# Board_no_0R.net
KiCad netlist of a schematic drawn in EAGLE
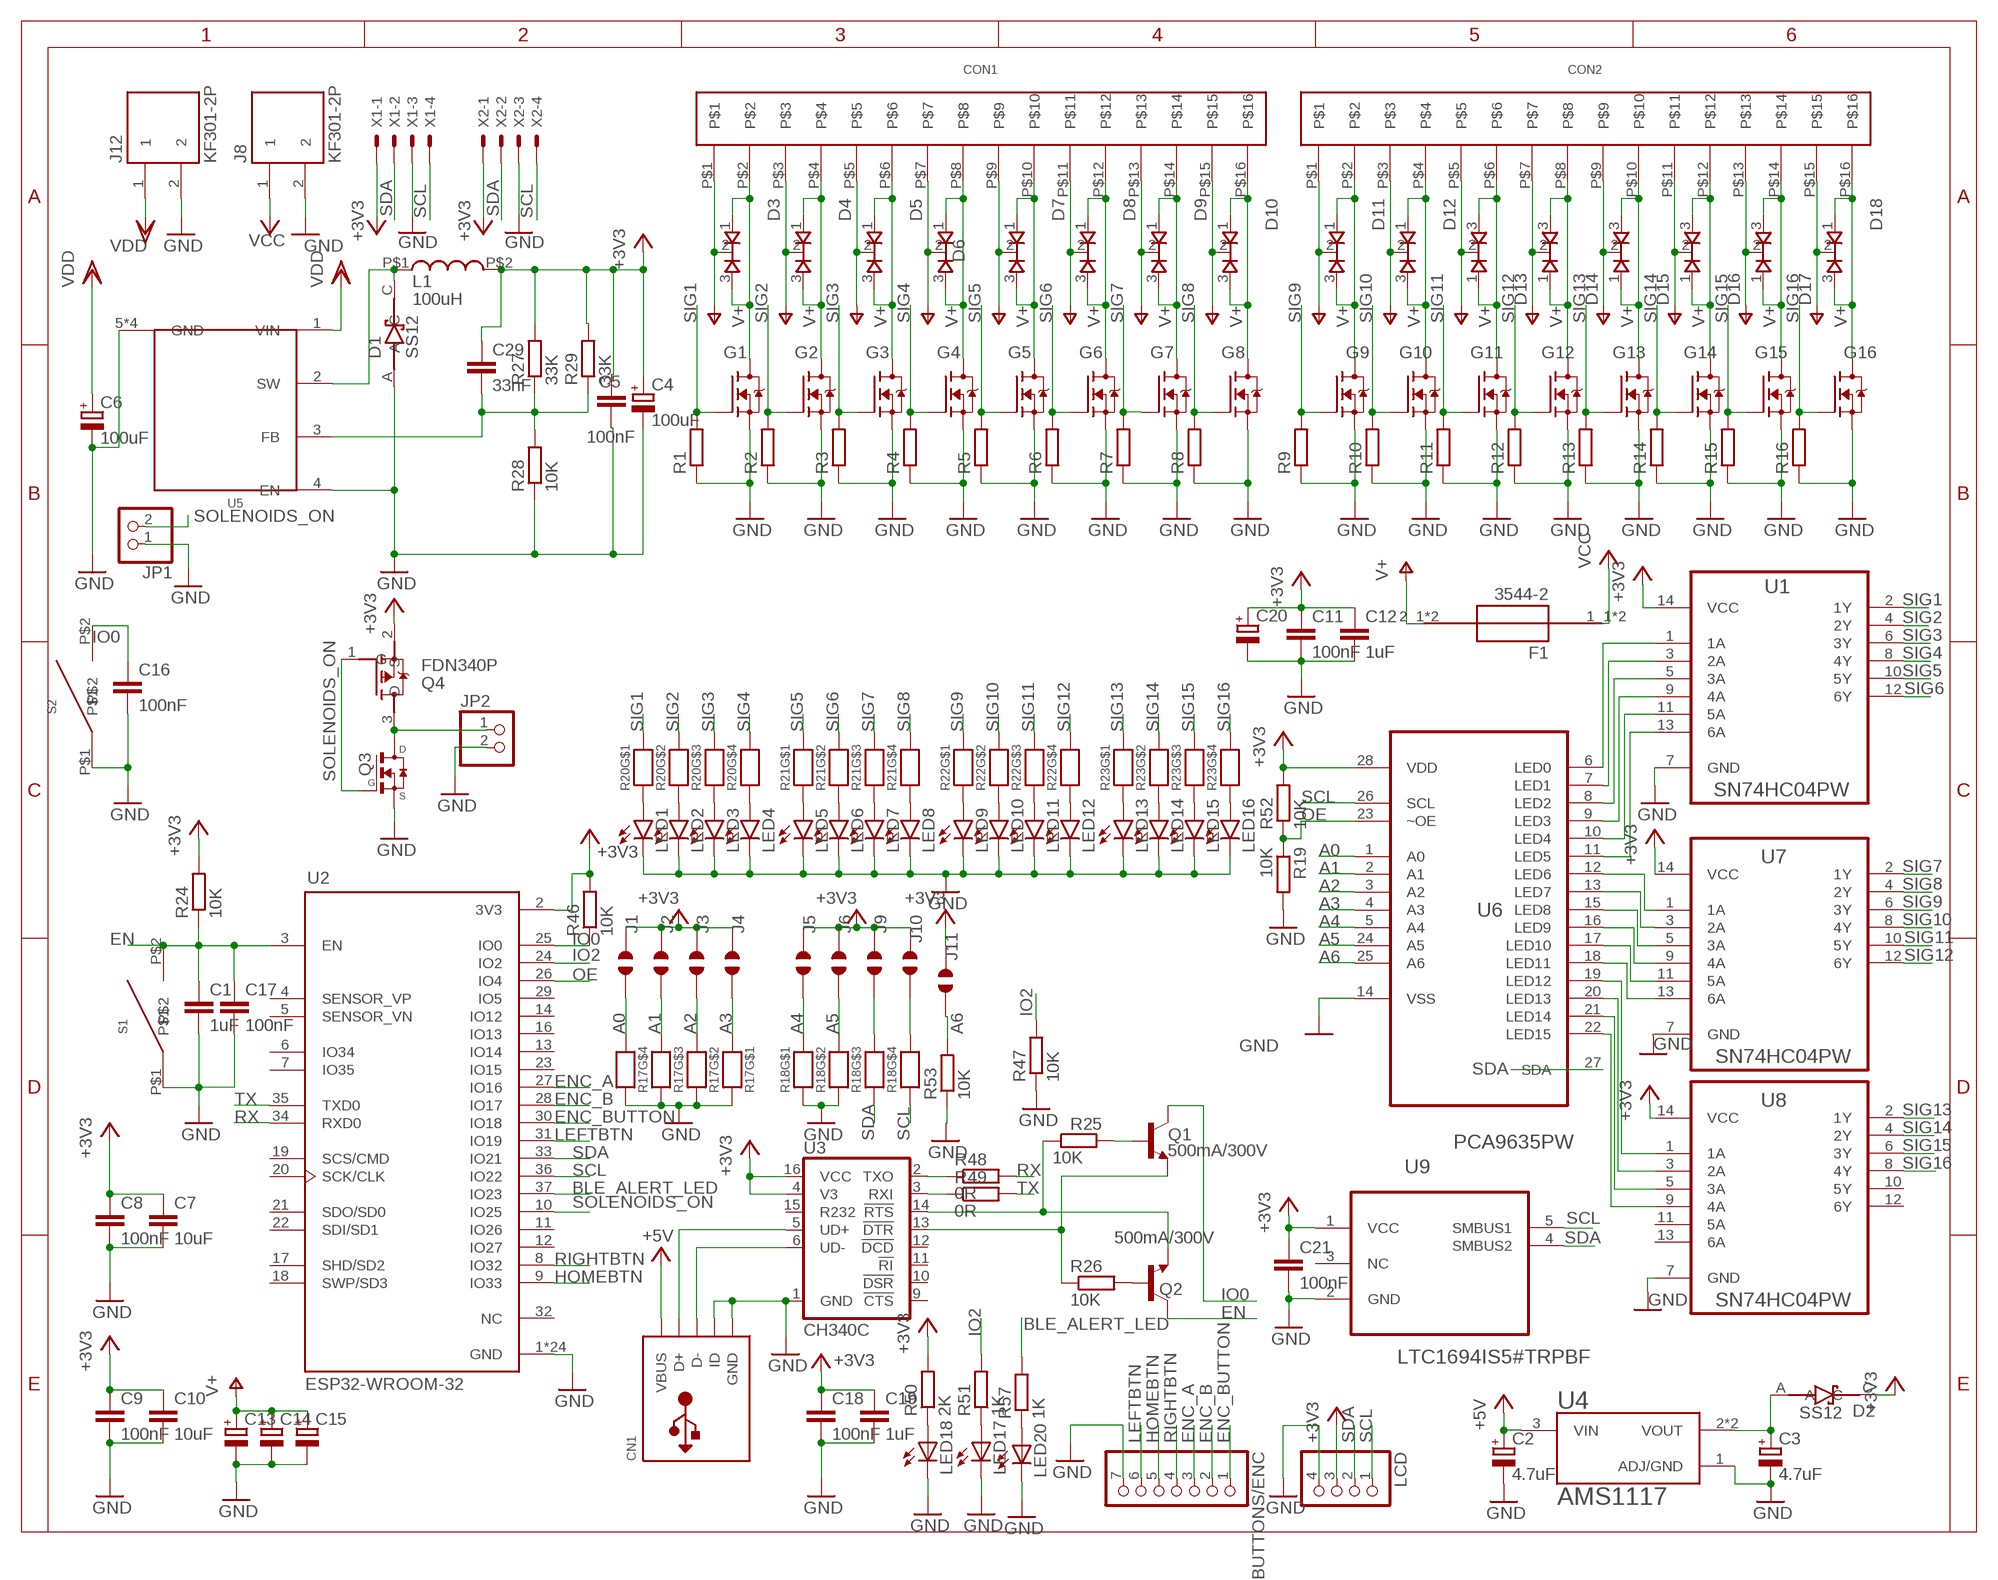
[diagram p0: schematic, sheet 1]

(export (version "E")
  (design (tool "Eeschema 10.0.6"))
  (components
    (comp (ref "BUTTONS/ENC")
      (value "PINHD-1X7")
      (footprint "eagle-import:1X07")
      (libsource (lib "eagle-import") (part "PINHD-1X7"))
    )
    (comp (ref "C1")
      (value "1uF")
      (footprint "eagle-import:C0603")
      (libsource (lib "eagle-import") (part "C-EUC0603"))
    )
    (comp (ref "C2")
      (value "4.7uF")
      (footprint "eagle-import:C_6032-28R")
      (libsource (lib "eagle-import") (part "CPOL-EUC/6032-28R"))
    )
    (comp (ref "C3")
      (value "4.7uF")
      (footprint "eagle-import:C_6032-28R")
      (libsource (lib "eagle-import") (part "CPOL-EUC/6032-28R"))
    )
    (comp (ref "C4")
      (value "100uF")
      (footprint "eagle-import:C_6032-28R")
      (libsource (lib "eagle-import") (part "CPOL-EUC/6032-28R"))
    )
    (comp (ref "C5")
      (value "100nF")
      (footprint "eagle-import:C0603")
      (libsource (lib "eagle-import") (part "C-EUC0603"))
    )
    (comp (ref "C6")
      (value "100uF")
      (footprint "eagle-import:C_6032-28R")
      (libsource (lib "eagle-import") (part "CPOL-EUC/6032-28R"))
    )
    (comp (ref "C7")
      (value "10uF")
      (footprint "eagle-import:C0603")
      (libsource (lib "eagle-import") (part "C-EUC0603"))
    )
    (comp (ref "C8")
      (value "100nF")
      (footprint "eagle-import:C0603")
      (libsource (lib "eagle-import") (part "C-EUC0603"))
    )
    (comp (ref "C9")
      (value "100nF")
      (footprint "eagle-import:C0603")
      (libsource (lib "eagle-import") (part "C-EUC0603"))
    )
    (comp (ref "C10")
      (value "10uF")
      (footprint "eagle-import:C0603")
      (libsource (lib "eagle-import") (part "C-EUC0603"))
    )
    (comp (ref "C11")
      (value "100nF")
      (footprint "eagle-import:C0603")
      (libsource (lib "eagle-import") (part "C-EUC0603"))
    )
    (comp (ref "C12")
      (value "1uF")
      (footprint "eagle-import:C0603")
      (libsource (lib "eagle-import") (part "C-EUC0603"))
    )
    (comp (ref "C13")
      (value "CPOL-EUE5-10.5")
      (footprint "eagle-import:E5-10,5")
      (libsource (lib "eagle-import") (part "CPOL-EUE5-10.5"))
    )
    (comp (ref "C14")
      (value "CPOL-EUE5-10.5")
      (footprint "eagle-import:E5-10,5")
      (libsource (lib "eagle-import") (part "CPOL-EUE5-10.5"))
    )
    (comp (ref "C15")
      (value "CPOL-EUE5-10.5")
      (footprint "eagle-import:E5-10,5")
      (libsource (lib "eagle-import") (part "CPOL-EUE5-10.5"))
    )
    (comp (ref "C16")
      (value "100nF")
      (footprint "eagle-import:C0603")
      (libsource (lib "eagle-import") (part "C-EUC0603"))
    )
    (comp (ref "C17")
      (value "100nF")
      (footprint "eagle-import:C0603")
      (libsource (lib "eagle-import") (part "C-EUC0603"))
    )
    (comp (ref "C18")
      (value "100nF")
      (footprint "eagle-import:C0603")
      (libsource (lib "eagle-import") (part "C-EUC0603"))
    )
    (comp (ref "C19")
      (value "1uF")
      (footprint "eagle-import:C0603")
      (libsource (lib "eagle-import") (part "C-EUC0603"))
    )
    (comp (ref "C20")
      (value "CPOL-EUB")
      (footprint "eagle-import:PANASONIC_B")
      (libsource (lib "eagle-import") (part "CPOL-EUB"))
    )
    (comp (ref "C21")
      (value "100nF")
      (footprint "eagle-import:C0603")
      (libsource (lib "eagle-import") (part "C-EUC0603"))
    )
    (comp (ref "C29")
      (value "33nF")
      (footprint "eagle-import:C0603")
      (libsource (lib "eagle-import") (part "C-EUC0603"))
    )
    (comp (ref "CN1")
      (value "USBMINIB")
      (footprint "eagle-import:USB-MINIB")
      (libsource (lib "eagle-import") (part "USBMINIB"))
    )
    (comp (ref "CON1")
      (value "2.54-16P")
      (footprint "eagle-import:2.54-16P")
      (libsource (lib "eagle-import") (part "2.54-16P"))
    )
    (comp (ref "CON2")
      (value "2.54-16P")
      (footprint "eagle-import:2.54-16P")
      (libsource (lib "eagle-import") (part "2.54-16P"))
    )
    (comp (ref "D1")
      (value "SS12")
      (footprint "eagle-import:DIOM4427X270N")
      (fields (field (name "MF") "ON Semiconductor"))
      (libsource (lib "eagle-import") (part "SS12"))
    )
    (comp (ref "D2")
      (value "SS12")
      (footprint "eagle-import:DIOM4427X270N")
      (fields (field (name "MF") "ON Semiconductor"))
      (libsource (lib "eagle-import") (part "SS12"))
    )
    (comp (ref "D3")
      (value "BYQ28E")
      (footprint "eagle-import:TO220V")
      (libsource (lib "eagle-import") (part "BYQ28E"))
    )
    (comp (ref "D4")
      (value "BYQ28E")
      (footprint "eagle-import:TO220V")
      (libsource (lib "eagle-import") (part "BYQ28E"))
    )
    (comp (ref "D5")
      (value "BYQ28E")
      (footprint "eagle-import:TO220V")
      (libsource (lib "eagle-import") (part "BYQ28E"))
    )
    (comp (ref "D6")
      (value "BYQ28E")
      (footprint "eagle-import:TO220V")
      (libsource (lib "eagle-import") (part "BYQ28E"))
    )
    (comp (ref "D7")
      (value "BYQ28E")
      (footprint "eagle-import:TO220V")
      (libsource (lib "eagle-import") (part "BYQ28E"))
    )
    (comp (ref "D8")
      (value "BYQ28E")
      (footprint "eagle-import:TO220V")
      (libsource (lib "eagle-import") (part "BYQ28E"))
    )
    (comp (ref "D9")
      (value "BYQ28E")
      (footprint "eagle-import:TO220V")
      (libsource (lib "eagle-import") (part "BYQ28E"))
    )
    (comp (ref "D10")
      (value "BYQ28E")
      (footprint "eagle-import:TO220V")
      (libsource (lib "eagle-import") (part "BYQ28E"))
    )
    (comp (ref "D11")
      (value "BYQ28E")
      (footprint "eagle-import:TO220V")
      (libsource (lib "eagle-import") (part "BYQ28E"))
    )
    (comp (ref "D12")
      (value "BYQ28E")
      (footprint "eagle-import:TO220V")
      (libsource (lib "eagle-import") (part "BYQ28E"))
    )
    (comp (ref "D13")
      (value "BYQ28E")
      (footprint "eagle-import:TO220V")
      (libsource (lib "eagle-import") (part "BYQ28E"))
    )
    (comp (ref "D14")
      (value "BYQ28E")
      (footprint "eagle-import:TO220V")
      (libsource (lib "eagle-import") (part "BYQ28E"))
    )
    (comp (ref "D15")
      (value "BYQ28E")
      (footprint "eagle-import:TO220V")
      (libsource (lib "eagle-import") (part "BYQ28E"))
    )
    (comp (ref "D16")
      (value "BYQ28E")
      (footprint "eagle-import:TO220V")
      (libsource (lib "eagle-import") (part "BYQ28E"))
    )
    (comp (ref "D17")
      (value "BYQ28E")
      (footprint "eagle-import:TO220V")
      (libsource (lib "eagle-import") (part "BYQ28E"))
    )
    (comp (ref "D18")
      (value "BYQ28E")
      (footprint "eagle-import:TO220V")
      (libsource (lib "eagle-import") (part "BYQ28E"))
    )
    (comp (ref "F1")
      (value "3544-2")
      (footprint "eagle-import:FUSE_3544-2")
      (fields (field (name "MF") "Keystone Electronics"))
      (libsource (lib "eagle-import") (part "3544-2"))
    )
    (comp (ref "G1")
      (value "IRL540N")
      (footprint "eagle-import:TO220V")
      (libsource (lib "eagle-import") (part "IRL540N"))
    )
    (comp (ref "G2")
      (value "IRL540N")
      (footprint "eagle-import:TO220V")
      (libsource (lib "eagle-import") (part "IRL540N"))
    )
    (comp (ref "G3")
      (value "IRL540N")
      (footprint "eagle-import:TO220V")
      (libsource (lib "eagle-import") (part "IRL540N"))
    )
    (comp (ref "G4")
      (value "IRL540N")
      (footprint "eagle-import:TO220V")
      (libsource (lib "eagle-import") (part "IRL540N"))
    )
    (comp (ref "G5")
      (value "IRL540N")
      (footprint "eagle-import:TO220V")
      (libsource (lib "eagle-import") (part "IRL540N"))
    )
    (comp (ref "G6")
      (value "IRL540N")
      (footprint "eagle-import:TO220V")
      (libsource (lib "eagle-import") (part "IRL540N"))
    )
    (comp (ref "G7")
      (value "IRL540N")
      (footprint "eagle-import:TO220V")
      (libsource (lib "eagle-import") (part "IRL540N"))
    )
    (comp (ref "G8")
      (value "IRL540N")
      (footprint "eagle-import:TO220V")
      (libsource (lib "eagle-import") (part "IRL540N"))
    )
    (comp (ref "G9")
      (value "IRL540N")
      (footprint "eagle-import:TO220V")
      (libsource (lib "eagle-import") (part "IRL540N"))
    )
    (comp (ref "G10")
      (value "IRL540N")
      (footprint "eagle-import:TO220V")
      (libsource (lib "eagle-import") (part "IRL540N"))
    )
    (comp (ref "G11")
      (value "IRL540N")
      (footprint "eagle-import:TO220V")
      (libsource (lib "eagle-import") (part "IRL540N"))
    )
    (comp (ref "G12")
      (value "IRL540N")
      (footprint "eagle-import:TO220V")
      (libsource (lib "eagle-import") (part "IRL540N"))
    )
    (comp (ref "G13")
      (value "IRL540N")
      (footprint "eagle-import:TO220V")
      (libsource (lib "eagle-import") (part "IRL540N"))
    )
    (comp (ref "G14")
      (value "IRL540N")
      (footprint "eagle-import:TO220V")
      (libsource (lib "eagle-import") (part "IRL540N"))
    )
    (comp (ref "G15")
      (value "IRL540N")
      (footprint "eagle-import:TO220V")
      (libsource (lib "eagle-import") (part "IRL540N"))
    )
    (comp (ref "G16")
      (value "IRL540N")
      (footprint "eagle-import:TO220V")
      (libsource (lib "eagle-import") (part "IRL540N"))
    )
    (comp (ref "J1")
      (value "JUMPER_SOLDER_1X2")
      (footprint "eagle-import:JUMPER_SOLDER_1X2")
      (libsource (lib "eagle-import") (part "JUMPER_SOLDER_1X2"))
    )
    (comp (ref "J2")
      (value "JUMPER_SOLDER_1X2")
      (footprint "eagle-import:JUMPER_SOLDER_1X2")
      (libsource (lib "eagle-import") (part "JUMPER_SOLDER_1X2"))
    )
    (comp (ref "J3")
      (value "JUMPER_SOLDER_1X2")
      (footprint "eagle-import:JUMPER_SOLDER_1X2")
      (libsource (lib "eagle-import") (part "JUMPER_SOLDER_1X2"))
    )
    (comp (ref "J4")
      (value "JUMPER_SOLDER_1X2")
      (footprint "eagle-import:JUMPER_SOLDER_1X2")
      (libsource (lib "eagle-import") (part "JUMPER_SOLDER_1X2"))
    )
    (comp (ref "J5")
      (value "JUMPER_SOLDER_1X2")
      (footprint "eagle-import:JUMPER_SOLDER_1X2")
      (libsource (lib "eagle-import") (part "JUMPER_SOLDER_1X2"))
    )
    (comp (ref "J6")
      (value "JUMPER_SOLDER_1X2")
      (footprint "eagle-import:JUMPER_SOLDER_1X2")
      (libsource (lib "eagle-import") (part "JUMPER_SOLDER_1X2"))
    )
    (comp (ref "J8")
      (value "KF301-2P")
      (footprint "eagle-import:KF301-2P")
      (fields (field (name "MF") "Handson Technology"))
      (libsource (lib "eagle-import") (part "KF301-2P"))
    )
    (comp (ref "J9")
      (value "JUMPER_SOLDER_1X2")
      (footprint "eagle-import:JUMPER_SOLDER_1X2")
      (libsource (lib "eagle-import") (part "JUMPER_SOLDER_1X2"))
    )
    (comp (ref "J10")
      (value "JUMPER_SOLDER_1X2")
      (footprint "eagle-import:JUMPER_SOLDER_1X2")
      (libsource (lib "eagle-import") (part "JUMPER_SOLDER_1X2"))
    )
    (comp (ref "J11")
      (value "JUMPER_SOLDER_1X2")
      (footprint "eagle-import:JUMPER_SOLDER_1X2")
      (libsource (lib "eagle-import") (part "JUMPER_SOLDER_1X2"))
    )
    (comp (ref "J12")
      (value "KF301-2P")
      (footprint "eagle-import:KF301-2P")
      (fields (field (name "MF") "Handson Technology"))
      (libsource (lib "eagle-import") (part "KF301-2P"))
    )
    (comp (ref "JP1")
      (value "PINHD-1X2")
      (footprint "eagle-import:1X02")
      (libsource (lib "eagle-import") (part "PINHD-1X2"))
    )
    (comp (ref "JP2")
      (value "PINHD-1X2")
      (footprint "eagle-import:1X02")
      (libsource (lib "eagle-import") (part "PINHD-1X2"))
    )
    (comp (ref "L1")
      (value "100uH")
      (footprint "eagle-import:CD43")
      (libsource (lib "eagle-import") (part "CD43"))
    )
    (comp (ref "LCD")
      (value "PINHD-1X4")
      (footprint "eagle-import:1X04")
      (libsource (lib "eagle-import") (part "PINHD-1X4"))
    )
    (comp (ref "LED1")
      (value "LEDSMT1206")
      (footprint "eagle-import:1206")
      (libsource (lib "eagle-import") (part "LEDSMT1206"))
    )
    (comp (ref "LED2")
      (value "LEDSMT1206")
      (footprint "eagle-import:1206")
      (libsource (lib "eagle-import") (part "LEDSMT1206"))
    )
    (comp (ref "LED3")
      (value "LEDSMT1206")
      (footprint "eagle-import:1206")
      (libsource (lib "eagle-import") (part "LEDSMT1206"))
    )
    (comp (ref "LED4")
      (value "LEDSMT1206")
      (footprint "eagle-import:1206")
      (libsource (lib "eagle-import") (part "LEDSMT1206"))
    )
    (comp (ref "LED5")
      (value "LEDSMT1206")
      (footprint "eagle-import:1206")
      (libsource (lib "eagle-import") (part "LEDSMT1206"))
    )
    (comp (ref "LED6")
      (value "LEDSMT1206")
      (footprint "eagle-import:1206")
      (libsource (lib "eagle-import") (part "LEDSMT1206"))
    )
    (comp (ref "LED7")
      (value "LEDSMT1206")
      (footprint "eagle-import:1206")
      (libsource (lib "eagle-import") (part "LEDSMT1206"))
    )
    (comp (ref "LED8")
      (value "LEDSMT1206")
      (footprint "eagle-import:1206")
      (libsource (lib "eagle-import") (part "LEDSMT1206"))
    )
    (comp (ref "LED9")
      (value "LEDSMT1206")
      (footprint "eagle-import:1206")
      (libsource (lib "eagle-import") (part "LEDSMT1206"))
    )
    (comp (ref "LED10")
      (value "LEDSMT1206")
      (footprint "eagle-import:1206")
      (libsource (lib "eagle-import") (part "LEDSMT1206"))
    )
    (comp (ref "LED11")
      (value "LEDSMT1206")
      (footprint "eagle-import:1206")
      (libsource (lib "eagle-import") (part "LEDSMT1206"))
    )
    (comp (ref "LED12")
      (value "LEDSMT1206")
      (footprint "eagle-import:1206")
      (libsource (lib "eagle-import") (part "LEDSMT1206"))
    )
    (comp (ref "LED13")
      (value "LEDSMT1206")
      (footprint "eagle-import:1206")
      (libsource (lib "eagle-import") (part "LEDSMT1206"))
    )
    (comp (ref "LED14")
      (value "LEDSMT1206")
      (footprint "eagle-import:1206")
      (libsource (lib "eagle-import") (part "LEDSMT1206"))
    )
    (comp (ref "LED15")
      (value "LEDSMT1206")
      (footprint "eagle-import:1206")
      (libsource (lib "eagle-import") (part "LEDSMT1206"))
    )
    (comp (ref "LED16")
      (value "LEDSMT1206")
      (footprint "eagle-import:1206")
      (libsource (lib "eagle-import") (part "LEDSMT1206"))
    )
    (comp (ref "LED17")
      (value "LED-0603")
      (footprint "eagle-import:LED-603")
      (libsource (lib "eagle-import") (part "LED-0603"))
    )
    (comp (ref "LED18")
      (value "LED-0603")
      (footprint "eagle-import:LED-603")
      (libsource (lib "eagle-import") (part "LED-0603"))
    )
    (comp (ref "LED20")
      (value "LED-0603")
      (footprint "eagle-import:LED-603")
      (libsource (lib "eagle-import") (part "LED-0603"))
    )
    (comp (ref "Q1")
      (value "500mA/300V")
      (footprint "eagle-import:SOT23-3")
      (libsource (lib "eagle-import") (part "TRANS_NPN-MMBTA42"))
    )
    (comp (ref "Q2")
      (value "500mA/300V")
      (footprint "eagle-import:SOT23-3")
      (libsource (lib "eagle-import") (part "TRANS_NPN-MMBTA42"))
    )
    (comp (ref "Q3")
      (value "FDN337N")
      (footprint "eagle-import:SSOT-3")
      (fields (field (name "MF") "ON Semiconductor"))
      (libsource (lib "eagle-import") (part "FDN337N"))
    )
    (comp (ref "Q4")
      (value "FDN340P")
      (footprint "eagle-import:SOT95P240X120-3N")
      (fields (field (name "MF") "ON Semiconductor"))
      (libsource (lib "eagle-import") (part "FDN340P"))
    )
    (comp (ref "R1")
      (value "R-EU_R0603")
      (footprint "eagle-import:R0603")
      (libsource (lib "eagle-import") (part "R-EU_R0603"))
    )
    (comp (ref "R2")
      (value "R-EU_R0603")
      (footprint "eagle-import:R0603")
      (libsource (lib "eagle-import") (part "R-EU_R0603"))
    )
    (comp (ref "R3")
      (value "R-EU_R0603")
      (footprint "eagle-import:R0603")
      (libsource (lib "eagle-import") (part "R-EU_R0603"))
    )
    (comp (ref "R4")
      (value "R-EU_R0603")
      (footprint "eagle-import:R0603")
      (libsource (lib "eagle-import") (part "R-EU_R0603"))
    )
    (comp (ref "R5")
      (value "R-EU_R0603")
      (footprint "eagle-import:R0603")
      (libsource (lib "eagle-import") (part "R-EU_R0603"))
    )
    (comp (ref "R6")
      (value "R-EU_R0603")
      (footprint "eagle-import:R0603")
      (libsource (lib "eagle-import") (part "R-EU_R0603"))
    )
    (comp (ref "R7")
      (value "R-EU_R0603")
      (footprint "eagle-import:R0603")
      (libsource (lib "eagle-import") (part "R-EU_R0603"))
    )
    (comp (ref "R8")
      (value "R-EU_R0603")
      (footprint "eagle-import:R0603")
      (libsource (lib "eagle-import") (part "R-EU_R0603"))
    )
    (comp (ref "R9")
      (value "R-EU_R0603")
      (footprint "eagle-import:R0603")
      (libsource (lib "eagle-import") (part "R-EU_R0603"))
    )
    (comp (ref "R10")
      (value "R-EU_R0603")
      (footprint "eagle-import:R0603")
      (libsource (lib "eagle-import") (part "R-EU_R0603"))
    )
    (comp (ref "R11")
      (value "R-EU_R0603")
      (footprint "eagle-import:R0603")
      (libsource (lib "eagle-import") (part "R-EU_R0603"))
    )
    (comp (ref "R12")
      (value "R-EU_R0603")
      (footprint "eagle-import:R0603")
      (libsource (lib "eagle-import") (part "R-EU_R0603"))
    )
    (comp (ref "R13")
      (value "R-EU_R0603")
      (footprint "eagle-import:R0603")
      (libsource (lib "eagle-import") (part "R-EU_R0603"))
    )
    (comp (ref "R14")
      (value "R-EU_R0603")
      (footprint "eagle-import:R0603")
      (libsource (lib "eagle-import") (part "R-EU_R0603"))
    )
    (comp (ref "R15")
      (value "R-EU_R0603")
      (footprint "eagle-import:R0603")
      (libsource (lib "eagle-import") (part "R-EU_R0603"))
    )
    (comp (ref "R16")
      (value "R-EU_R0603")
      (footprint "eagle-import:R0603")
      (libsource (lib "eagle-import") (part "R-EU_R0603"))
    )
    (comp (ref "R17")
      (value "MICROBUILDER_RESISTOR_4PACK")
      (footprint "eagle-import:MICROBUILDER_RESPACK_4X0603")
      (libsource (lib "eagle-import") (part "MICROBUILDER_RESISTOR_4PACK"))
    )
    (comp (ref "R18")
      (value "MICROBUILDER_RESISTOR_4PACK")
      (footprint "eagle-import:MICROBUILDER_RESPACK_4X0603")
      (libsource (lib "eagle-import") (part "MICROBUILDER_RESISTOR_4PACK"))
    )
    (comp (ref "R19")
      (value "10K")
      (footprint "eagle-import:R1206")
      (libsource (lib "eagle-import") (part "R-EU_R1206"))
    )
    (comp (ref "R20")
      (value "MICROBUILDER_RESISTOR_4PACK")
      (footprint "eagle-import:MICROBUILDER_RESPACK_4X0603")
      (libsource (lib "eagle-import") (part "MICROBUILDER_RESISTOR_4PACK"))
    )
    (comp (ref "R21")
      (value "MICROBUILDER_RESISTOR_4PACK")
      (footprint "eagle-import:MICROBUILDER_RESPACK_4X0603")
      (libsource (lib "eagle-import") (part "MICROBUILDER_RESISTOR_4PACK"))
    )
    (comp (ref "R22")
      (value "MICROBUILDER_RESISTOR_4PACK")
      (footprint "eagle-import:MICROBUILDER_RESPACK_4X0603")
      (libsource (lib "eagle-import") (part "MICROBUILDER_RESISTOR_4PACK"))
    )
    (comp (ref "R23")
      (value "MICROBUILDER_RESISTOR_4PACK")
      (footprint "eagle-import:MICROBUILDER_RESPACK_4X0603")
      (libsource (lib "eagle-import") (part "MICROBUILDER_RESISTOR_4PACK"))
    )
    (comp (ref "R24")
      (value "10K")
      (footprint "eagle-import:R0603")
      (libsource (lib "eagle-import") (part "R-EU_R0603"))
    )
    (comp (ref "R25")
      (value "10K")
      (footprint "eagle-import:R0603")
      (libsource (lib "eagle-import") (part "R-EU_R0603"))
    )
    (comp (ref "R26")
      (value "10K")
      (footprint "eagle-import:R0603")
      (libsource (lib "eagle-import") (part "R-EU_R0603"))
    )
    (comp (ref "R27")
      (value "33K")
      (footprint "eagle-import:R0603")
      (libsource (lib "eagle-import") (part "R-EU_R0603"))
    )
    (comp (ref "R28")
      (value "10K")
      (footprint "eagle-import:R0603")
      (libsource (lib "eagle-import") (part "R-EU_R0603"))
    )
    (comp (ref "R29")
      (value "33K")
      (footprint "eagle-import:R0603")
      (libsource (lib "eagle-import") (part "R-EU_R0603"))
    )
    (comp (ref "R46")
      (value "10K")
      (footprint "eagle-import:R0603")
      (libsource (lib "eagle-import") (part "R-EU_R0603"))
    )
    (comp (ref "R47")
      (value "10K")
      (footprint "eagle-import:R0603")
      (libsource (lib "eagle-import") (part "R-EU_R0603"))
    )
    (comp (ref "R48")
      (value "0R")
      (footprint "eagle-import:R0603")
      (libsource (lib "eagle-import") (part "R-EU_R0603"))
    )
    (comp (ref "R49")
      (value "0R")
      (footprint "eagle-import:R0603")
      (libsource (lib "eagle-import") (part "R-EU_R0603"))
    )
    (comp (ref "R50")
      (value "2K")
      (footprint "eagle-import:R0603")
      (libsource (lib "eagle-import") (part "R-EU_R0603"))
    )
    (comp (ref "R51")
      (value "1K")
      (footprint "eagle-import:R0603")
      (libsource (lib "eagle-import") (part "R-EU_R0603"))
    )
    (comp (ref "R52")
      (value "10K")
      (footprint "eagle-import:R0603")
      (libsource (lib "eagle-import") (part "R-EU_R0603"))
    )
    (comp (ref "R53")
      (value "10K")
      (footprint "eagle-import:R0603")
      (libsource (lib "eagle-import") (part "R-EU_R0603"))
    )
    (comp (ref "R57")
      (value "1K")
      (footprint "eagle-import:R0603")
      (libsource (lib "eagle-import") (part "R-EU_R0603"))
    )
    (comp (ref "S1")
      (value "3X6X2.5")
      (footprint "eagle-import:3X6X2.5")
      (libsource (lib "eagle-import") (part "3X6X2.5"))
    )
    (comp (ref "S2")
      (value "3X6X2.5")
      (footprint "eagle-import:3X6X2.5")
      (libsource (lib "eagle-import") (part "3X6X2.5"))
    )
    (comp (ref "U1")
      (value "SN74HC04PW")
      (footprint "eagle-import:SOP65P640X120-14N")
      (libsource (lib "eagle-import") (part "SN74HC04PW"))
    )
    (comp (ref "U2")
      (value "ESP32-WROOM-32")
      (footprint "eagle-import:MODULE_ESP32-WROOM-32")
      (fields (field (name "MF") "Espressif Systems"))
      (libsource (lib "eagle-import") (part "ESP32-WROOM-32"))
    )
    (comp (ref "U3")
      (value "CH340C")
      (footprint "eagle-import:SO016")
      (fields (field (name "MF") "WCH"))
      (libsource (lib "eagle-import") (part "CH340C"))
    )
    (comp (ref "U4")
      (value "AMS1117")
      (footprint "eagle-import:SOT229P700X180-4N")
      (fields (field (name "MF") "Advanced Monolithic Systems"))
      (libsource (lib "eagle-import") (part "AMS1117"))
    )
    (comp (ref "U5")
      (value "XL7005A")
      (footprint "eagle-import:SO8")
      (libsource (lib "eagle-import") (part "XL7005A"))
    )
    (comp (ref "U6")
      (value "PCA9635PW")
      (footprint "eagle-import:SOP65P640X110-28N")
      (fields (field (name "MF") "NXP Semiconductors"))
      (libsource (lib "eagle-import") (part "PCA9635PW"))
    )
    (comp (ref "U7")
      (value "SN74HC04PW")
      (footprint "eagle-import:SOP65P640X120-14N")
      (libsource (lib "eagle-import") (part "SN74HC04PW"))
    )
    (comp (ref "U8")
      (value "SN74HC04PW")
      (footprint "eagle-import:SOP65P640X120-14N")
      (libsource (lib "eagle-import") (part "SN74HC04PW"))
    )
    (comp (ref "U9")
      (value "LTC1694IS5#TRPBF")
      (footprint "eagle-import:SOT95P280X100-5N")
      (fields (field (name "MF") "Analog Devices"))
      (libsource (lib "eagle-import") (part "LTC1694IS5#TRPBF"))
    )
    (comp (ref "X1")
      (value "JST-XH-04-PIN-LONG-PAD")
      (footprint "eagle-import:JST-XH-04-PACKAGE-LONG-PAD")
      (libsource (lib "eagle-import") (part "JST-XH-04-PIN-LONG-PAD"))
    )
    (comp (ref "X2")
      (value "JST-XH-04-PIN-LONG-PAD")
      (footprint "eagle-import:JST-XH-04-PACKAGE-LONG-PAD")
      (libsource (lib "eagle-import") (part "JST-XH-04-PIN-LONG-PAD"))
    )
  )
  (nets
    (net (code "1") (name "+3V3") (class "Default")
      (node (ref "C10") (pin "1") (pinfunction "1_1") (pintype "passive"))
      (node (ref "C11") (pin "1") (pinfunction "1_1") (pintype "passive"))
      (node (ref "C12") (pin "1") (pinfunction "1_1") (pintype "passive"))
      (node (ref "C18") (pin "1") (pinfunction "1_1") (pintype "passive"))
      (node (ref "C19") (pin "1") (pinfunction "1_1") (pintype "passive"))
      (node (ref "C20") (pin "+") (pinfunction "+_+") (pintype "passive"))
      (node (ref "C21") (pin "1") (pinfunction "1_1") (pintype "passive"))
      (node (ref "C29") (pin "1") (pinfunction "1_1") (pintype "passive"))
      (node (ref "C4") (pin "+") (pinfunction "+_+") (pintype "passive"))
      (node (ref "C5") (pin "1") (pinfunction "1_1") (pintype "passive"))
      (node (ref "C7") (pin "1") (pinfunction "1_1") (pintype "passive"))
      (node (ref "C8") (pin "1") (pinfunction "1_1") (pintype "passive"))
      (node (ref "C9") (pin "1") (pinfunction "1_1") (pintype "passive"))
      (node (ref "D2") (pin "C") (pinfunction "C_C") (pintype "passive"))
      (node (ref "J1") (pin "1") (pinfunction "1_1") (pintype "passive"))
      (node (ref "J10") (pin "1") (pinfunction "1_1") (pintype "passive"))
      (node (ref "J11") (pin "1") (pinfunction "1_1") (pintype "passive"))
      (node (ref "J2") (pin "1") (pinfunction "1_1") (pintype "passive"))
      (node (ref "J3") (pin "1") (pinfunction "1_1") (pintype "passive"))
      (node (ref "J4") (pin "1") (pinfunction "1_1") (pintype "passive"))
      (node (ref "J5") (pin "1") (pinfunction "1_1") (pintype "passive"))
      (node (ref "J6") (pin "1") (pinfunction "1_1") (pintype "passive"))
      (node (ref "J9") (pin "1") (pinfunction "1_1") (pintype "passive"))
      (node (ref "L1") (pin "P$2") (pinfunction "P$2_P$2") (pintype "bidirectional"))
      (node (ref "LCD") (pin "3") (pinfunction "3_3") (pintype "passive"))
      (node (ref "Q4") (pin "2") (pinfunction "S_2") (pintype "passive"))
      (node (ref "R24") (pin "2") (pinfunction "2_2") (pintype "passive"))
      (node (ref "R27") (pin "2") (pinfunction "2_2") (pintype "passive"))
      (node (ref "R29") (pin "2") (pinfunction "2_2") (pintype "passive"))
      (node (ref "R46") (pin "2") (pinfunction "2_2") (pintype "passive"))
      (node (ref "R50") (pin "2") (pinfunction "2_2") (pintype "passive"))
      (node (ref "R52") (pin "2") (pinfunction "2_2") (pintype "passive"))
      (node (ref "U1") (pin "14") (pinfunction "VCC_14") (pintype "power_in"))
      (node (ref "U2") (pin "2") (pinfunction "3V3_2") (pintype "power_in"))
      (node (ref "U3") (pin "16") (pinfunction "VCC_16") (pintype "bidirectional"))
      (node (ref "U3") (pin "4") (pinfunction "V3_4") (pintype "bidirectional"))
      (node (ref "U6") (pin "28") (pinfunction "VDD_28") (pintype "power_in"))
      (node (ref "U7") (pin "14") (pinfunction "VCC_14") (pintype "power_in"))
      (node (ref "U8") (pin "14") (pinfunction "VCC_14") (pintype "power_in"))
      (node (ref "U9") (pin "1") (pinfunction "VCC_1") (pintype "power_in"))
      (node (ref "X1") (pin "1") (pinfunction "S_1") (pintype "passive"))
      (node (ref "X2") (pin "1") (pinfunction "S_1") (pintype "passive"))
    )
    (net (code "2") (name "+5V") (class "Default")
      (node (ref "C2") (pin "+") (pinfunction "+_+") (pintype "passive"))
      (node (ref "CN1") (pin "VBUS") (pinfunction "VBUS_VBUS") (pintype "power_in"))
      (node (ref "U4") (pin "3") (pinfunction "VIN_3") (pintype "input"))
    )
    (net (code "3") (name "/A0") (class "Default")
      (node (ref "J1") (pin "2") (pinfunction "2_2") (pintype "passive"))
      (node (ref "R17") (pin "4") (pinfunction "1_4") (pintype "passive"))
      (node (ref "U6") (pin "1") (pinfunction "A0_1") (pintype "input"))
    )
    (net (code "4") (name "/A1") (class "Default")
      (node (ref "J2") (pin "2") (pinfunction "2_2") (pintype "passive"))
      (node (ref "R17") (pin "3") (pinfunction "1_3") (pintype "passive"))
      (node (ref "U6") (pin "2") (pinfunction "A1_2") (pintype "input"))
    )
    (net (code "5") (name "/A2") (class "Default")
      (node (ref "J3") (pin "2") (pinfunction "2_2") (pintype "passive"))
      (node (ref "R17") (pin "2") (pinfunction "1_2") (pintype "passive"))
      (node (ref "U6") (pin "3") (pinfunction "A2_3") (pintype "input"))
    )
    (net (code "6") (name "/A3") (class "Default")
      (node (ref "J4") (pin "2") (pinfunction "2_2") (pintype "passive"))
      (node (ref "R17") (pin "1") (pinfunction "1_1") (pintype "passive"))
      (node (ref "U6") (pin "4") (pinfunction "A3_4") (pintype "input"))
    )
    (net (code "7") (name "/A4") (class "Default")
      (node (ref "J5") (pin "2") (pinfunction "2_2") (pintype "passive"))
      (node (ref "R18") (pin "8") (pinfunction "2_8") (pintype "passive"))
      (node (ref "U6") (pin "5") (pinfunction "A4_5") (pintype "input"))
    )
    (net (code "8") (name "/A5") (class "Default")
      (node (ref "J6") (pin "2") (pinfunction "2_2") (pintype "passive"))
      (node (ref "R18") (pin "7") (pinfunction "2_7") (pintype "passive"))
      (node (ref "U6") (pin "24") (pinfunction "A5_24") (pintype "input"))
    )
    (net (code "9") (name "/A6") (class "Default")
      (node (ref "J11") (pin "2") (pinfunction "2_2") (pintype "passive"))
      (node (ref "R53") (pin "2") (pinfunction "2_2") (pintype "passive"))
      (node (ref "U6") (pin "25") (pinfunction "A6_25") (pintype "input"))
    )
    (net (code "10") (name "/BLE_ALERT_LED") (class "Default")
      (node (ref "R57") (pin "2") (pinfunction "2_2") (pintype "passive"))
      (node (ref "U2") (pin "37") (pinfunction "IO23_37") (pintype "bidirectional"))
    )
    (net (code "11") (name "/EN") (class "Default")
      (node (ref "C1") (pin "1") (pinfunction "1_1") (pintype "passive"))
      (node (ref "C17") (pin "1") (pinfunction "1_1") (pintype "passive"))
      (node (ref "Q2") (pin "3") (pinfunction "C_3") (pintype "passive"))
      (node (ref "R24") (pin "1") (pinfunction "1_1") (pintype "passive"))
      (node (ref "S1") (pin "P$2") (pinfunction "P$2_P$2") (pintype "bidirectional"))
      (node (ref "U2") (pin "3") (pinfunction "EN_3") (pintype "input"))
    )
    (net (code "12") (name "/ENC_A") (class "Default")
      (node (ref "BUTTONS/ENC") (pin "3") (pinfunction "3_3") (pintype "passive"))
      (node (ref "U2") (pin "27") (pinfunction "IO16_27") (pintype "bidirectional"))
    )
    (net (code "13") (name "/ENC_B") (class "Default")
      (node (ref "BUTTONS/ENC") (pin "2") (pinfunction "2_2") (pintype "passive"))
      (node (ref "U2") (pin "28") (pinfunction "IO17_28") (pintype "bidirectional"))
    )
    (net (code "14") (name "/ENC_BUTTON") (class "Default")
      (node (ref "BUTTONS/ENC") (pin "1") (pinfunction "1_1") (pintype "passive"))
      (node (ref "U2") (pin "30") (pinfunction "IO18_30") (pintype "bidirectional"))
    )
    (net (code "15") (name "/HOMEBTN") (class "Default")
      (node (ref "BUTTONS/ENC") (pin "5") (pinfunction "5_5") (pintype "passive"))
      (node (ref "U2") (pin "9") (pinfunction "IO33_9") (pintype "bidirectional"))
    )
    (net (code "16") (name "/IO0") (class "Default")
      (node (ref "C16") (pin "1") (pinfunction "1_1") (pintype "passive"))
      (node (ref "Q1") (pin "3") (pinfunction "C_3") (pintype "passive"))
      (node (ref "R46") (pin "1") (pinfunction "1_1") (pintype "passive"))
      (node (ref "S2") (pin "P$2") (pinfunction "P$2_P$2") (pintype "bidirectional"))
      (node (ref "U2") (pin "25") (pinfunction "IO0_25") (pintype "bidirectional"))
    )
    (net (code "17") (name "/IO2") (class "Default")
      (node (ref "R47") (pin "2") (pinfunction "2_2") (pintype "passive"))
      (node (ref "R51") (pin "2") (pinfunction "2_2") (pintype "passive"))
      (node (ref "U2") (pin "24") (pinfunction "IO2_24") (pintype "bidirectional"))
    )
    (net (code "18") (name "/LEFTBTN") (class "Default")
      (node (ref "BUTTONS/ENC") (pin "6") (pinfunction "6_6") (pintype "passive"))
      (node (ref "U2") (pin "31") (pinfunction "IO19_31") (pintype "bidirectional"))
    )
    (net (code "19") (name "/OE") (class "Default")
      (node (ref "R19") (pin "1") (pinfunction "1_1") (pintype "passive"))
      (node (ref "R52") (pin "1") (pinfunction "1_1") (pintype "passive"))
      (node (ref "U2") (pin "26") (pinfunction "IO4_26") (pintype "bidirectional"))
      (node (ref "U6") (pin "23") (pinfunction "~{OE}_23") (pintype "input"))
    )
    (net (code "20") (name "/RIGHTBTN") (class "Default")
      (node (ref "BUTTONS/ENC") (pin "4") (pinfunction "4_4") (pintype "passive"))
      (node (ref "U2") (pin "8") (pinfunction "IO32_8") (pintype "bidirectional"))
    )
    (net (code "21") (name "/RX") (class "Default")
      (node (ref "R48") (pin "2") (pinfunction "2_2") (pintype "passive"))
      (node (ref "U2") (pin "34") (pinfunction "RXD0_34") (pintype "bidirectional"))
    )
    (net (code "22") (name "/SCL") (class "Default")
      (node (ref "LCD") (pin "1") (pinfunction "1_1") (pintype "passive"))
      (node (ref "R18") (pin "4") (pinfunction "1_4") (pintype "passive"))
      (node (ref "U2") (pin "36") (pinfunction "IO22_36") (pintype "bidirectional"))
      (node (ref "U6") (pin "26") (pinfunction "SCL_26") (pintype "input"))
      (node (ref "U9") (pin "5") (pinfunction "SMBUS1_5") (pintype "passive"))
      (node (ref "X1") (pin "4") (pinfunction "S_4") (pintype "passive"))
      (node (ref "X2") (pin "4") (pinfunction "S_4") (pintype "passive"))
    )
    (net (code "23") (name "/SDA") (class "Default")
      (node (ref "LCD") (pin "2") (pinfunction "2_2") (pintype "passive"))
      (node (ref "R18") (pin "3") (pinfunction "1_3") (pintype "passive"))
      (node (ref "U2") (pin "33") (pinfunction "IO21_33") (pintype "bidirectional"))
      (node (ref "U6") (pin "27") (pinfunction "SDA_27") (pintype "bidirectional"))
      (node (ref "U9") (pin "4") (pinfunction "SMBUS2_4") (pintype "passive"))
      (node (ref "X1") (pin "2") (pinfunction "S_2") (pintype "passive"))
      (node (ref "X2") (pin "2") (pinfunction "S_2") (pintype "passive"))
    )
    (net (code "24") (name "/SIG1") (class "Default")
      (node (ref "G1") (pin "1") (pinfunction "G_1") (pintype "passive"))
      (node (ref "R1") (pin "2") (pinfunction "2_2") (pintype "passive"))
      (node (ref "R20") (pin "8") (pinfunction "2_8") (pintype "passive"))
      (node (ref "U1") (pin "2") (pinfunction "1Y_2") (pintype "output"))
    )
    (net (code "25") (name "/SIG2") (class "Default")
      (node (ref "G2") (pin "1") (pinfunction "G_1") (pintype "passive"))
      (node (ref "R2") (pin "2") (pinfunction "2_2") (pintype "passive"))
      (node (ref "R20") (pin "7") (pinfunction "2_7") (pintype "passive"))
      (node (ref "U1") (pin "4") (pinfunction "2Y_4") (pintype "output"))
    )
    (net (code "26") (name "/SIG3") (class "Default")
      (node (ref "G3") (pin "1") (pinfunction "G_1") (pintype "passive"))
      (node (ref "R20") (pin "6") (pinfunction "2_6") (pintype "passive"))
      (node (ref "R3") (pin "2") (pinfunction "2_2") (pintype "passive"))
      (node (ref "U1") (pin "6") (pinfunction "3Y_6") (pintype "output"))
    )
    (net (code "27") (name "/SIG4") (class "Default")
      (node (ref "G4") (pin "1") (pinfunction "G_1") (pintype "passive"))
      (node (ref "R20") (pin "5") (pinfunction "2_5") (pintype "passive"))
      (node (ref "R4") (pin "2") (pinfunction "2_2") (pintype "passive"))
      (node (ref "U1") (pin "8") (pinfunction "4Y_8") (pintype "output"))
    )
    (net (code "28") (name "/SIG5") (class "Default")
      (node (ref "G5") (pin "1") (pinfunction "G_1") (pintype "passive"))
      (node (ref "R21") (pin "8") (pinfunction "2_8") (pintype "passive"))
      (node (ref "R5") (pin "2") (pinfunction "2_2") (pintype "passive"))
      (node (ref "U1") (pin "10") (pinfunction "5Y_10") (pintype "output"))
    )
    (net (code "29") (name "/SIG6") (class "Default")
      (node (ref "G6") (pin "1") (pinfunction "G_1") (pintype "passive"))
      (node (ref "R21") (pin "7") (pinfunction "2_7") (pintype "passive"))
      (node (ref "R6") (pin "2") (pinfunction "2_2") (pintype "passive"))
      (node (ref "U1") (pin "12") (pinfunction "6Y_12") (pintype "output"))
    )
    (net (code "30") (name "/SIG7") (class "Default")
      (node (ref "G7") (pin "1") (pinfunction "G_1") (pintype "passive"))
      (node (ref "R21") (pin "6") (pinfunction "2_6") (pintype "passive"))
      (node (ref "R7") (pin "2") (pinfunction "2_2") (pintype "passive"))
      (node (ref "U7") (pin "2") (pinfunction "1Y_2") (pintype "output"))
    )
    (net (code "31") (name "/SIG8") (class "Default")
      (node (ref "G8") (pin "1") (pinfunction "G_1") (pintype "passive"))
      (node (ref "R21") (pin "5") (pinfunction "2_5") (pintype "passive"))
      (node (ref "R8") (pin "2") (pinfunction "2_2") (pintype "passive"))
      (node (ref "U7") (pin "4") (pinfunction "2Y_4") (pintype "output"))
    )
    (net (code "32") (name "/SIG9") (class "Default")
      (node (ref "G9") (pin "1") (pinfunction "G_1") (pintype "passive"))
      (node (ref "R22") (pin "8") (pinfunction "2_8") (pintype "passive"))
      (node (ref "R9") (pin "2") (pinfunction "2_2") (pintype "passive"))
      (node (ref "U7") (pin "6") (pinfunction "3Y_6") (pintype "output"))
    )
    (net (code "33") (name "/SIG10") (class "Default")
      (node (ref "G10") (pin "1") (pinfunction "G_1") (pintype "passive"))
      (node (ref "R10") (pin "2") (pinfunction "2_2") (pintype "passive"))
      (node (ref "R22") (pin "7") (pinfunction "2_7") (pintype "passive"))
      (node (ref "U7") (pin "8") (pinfunction "4Y_8") (pintype "output"))
    )
    (net (code "34") (name "/SIG11") (class "Default")
      (node (ref "G11") (pin "1") (pinfunction "G_1") (pintype "passive"))
      (node (ref "R11") (pin "2") (pinfunction "2_2") (pintype "passive"))
      (node (ref "R22") (pin "6") (pinfunction "2_6") (pintype "passive"))
      (node (ref "U7") (pin "10") (pinfunction "5Y_10") (pintype "output"))
    )
    (net (code "35") (name "/SIG12") (class "Default")
      (node (ref "G12") (pin "1") (pinfunction "G_1") (pintype "passive"))
      (node (ref "R12") (pin "2") (pinfunction "2_2") (pintype "passive"))
      (node (ref "R22") (pin "5") (pinfunction "2_5") (pintype "passive"))
      (node (ref "U7") (pin "12") (pinfunction "6Y_12") (pintype "output"))
    )
    (net (code "36") (name "/SIG13") (class "Default")
      (node (ref "G13") (pin "1") (pinfunction "G_1") (pintype "passive"))
      (node (ref "R13") (pin "2") (pinfunction "2_2") (pintype "passive"))
      (node (ref "R23") (pin "8") (pinfunction "2_8") (pintype "passive"))
      (node (ref "U8") (pin "2") (pinfunction "1Y_2") (pintype "output"))
    )
    (net (code "37") (name "/SIG14") (class "Default")
      (node (ref "G14") (pin "1") (pinfunction "G_1") (pintype "passive"))
      (node (ref "R14") (pin "2") (pinfunction "2_2") (pintype "passive"))
      (node (ref "R23") (pin "7") (pinfunction "2_7") (pintype "passive"))
      (node (ref "U8") (pin "4") (pinfunction "2Y_4") (pintype "output"))
    )
    (net (code "38") (name "/SIG15") (class "Default")
      (node (ref "G15") (pin "1") (pinfunction "G_1") (pintype "passive"))
      (node (ref "R15") (pin "2") (pinfunction "2_2") (pintype "passive"))
      (node (ref "R23") (pin "6") (pinfunction "2_6") (pintype "passive"))
      (node (ref "U8") (pin "6") (pinfunction "3Y_6") (pintype "output"))
    )
    (net (code "39") (name "/SIG16") (class "Default")
      (node (ref "G16") (pin "1") (pinfunction "G_1") (pintype "passive"))
      (node (ref "R16") (pin "2") (pinfunction "2_2") (pintype "passive"))
      (node (ref "R23") (pin "5") (pinfunction "2_5") (pintype "passive"))
      (node (ref "U8") (pin "8") (pinfunction "4Y_8") (pintype "output"))
    )
    (net (code "40") (name "/SOLENOIDS_ON") (class "Default")
      (node (ref "JP1") (pin "2") (pinfunction "2_2") (pintype "passive"))
      (node (ref "Q3") (pin "1") (pinfunction "G_1") (pintype "passive"))
      (node (ref "Q4") (pin "1") (pinfunction "G_1") (pintype "passive"))
      (node (ref "U2") (pin "10") (pinfunction "IO25_10") (pintype "bidirectional"))
    )
    (net (code "41") (name "/TX") (class "Default")
      (node (ref "R49") (pin "2") (pinfunction "2_2") (pintype "passive"))
      (node (ref "U2") (pin "35") (pinfunction "TXD0_35") (pintype "bidirectional"))
    )
    (net (code "42") (name "GND") (class "Default")
      (node (ref "BUTTONS/ENC") (pin "7") (pinfunction "7_7") (pintype "passive"))
      (node (ref "C1") (pin "2") (pinfunction "2_2") (pintype "passive"))
      (node (ref "C10") (pin "2") (pinfunction "2_2") (pintype "passive"))
      (node (ref "C11") (pin "2") (pinfunction "2_2") (pintype "passive"))
      (node (ref "C12") (pin "2") (pinfunction "2_2") (pintype "passive"))
      (node (ref "C13") (pin "-") (pinfunction "-_-") (pintype "passive"))
      (node (ref "C14") (pin "-") (pinfunction "-_-") (pintype "passive"))
      (node (ref "C15") (pin "-") (pinfunction "-_-") (pintype "passive"))
      (node (ref "C16") (pin "2") (pinfunction "2_2") (pintype "passive"))
      (node (ref "C17") (pin "2") (pinfunction "2_2") (pintype "passive"))
      (node (ref "C18") (pin "2") (pinfunction "2_2") (pintype "passive"))
      (node (ref "C19") (pin "2") (pinfunction "2_2") (pintype "passive"))
      (node (ref "C2") (pin "-") (pinfunction "-_-") (pintype "passive"))
      (node (ref "C20") (pin "-") (pinfunction "-_-") (pintype "passive"))
      (node (ref "C21") (pin "2") (pinfunction "2_2") (pintype "passive"))
      (node (ref "C3") (pin "-") (pinfunction "-_-") (pintype "passive"))
      (node (ref "C4") (pin "-") (pinfunction "-_-") (pintype "passive"))
      (node (ref "C5") (pin "2") (pinfunction "2_2") (pintype "passive"))
      (node (ref "C6") (pin "-") (pinfunction "-_-") (pintype "passive"))
      (node (ref "C7") (pin "2") (pinfunction "2_2") (pintype "passive"))
      (node (ref "C8") (pin "2") (pinfunction "2_2") (pintype "passive"))
      (node (ref "C9") (pin "2") (pinfunction "2_2") (pintype "passive"))
      (node (ref "CN1") (pin "GND") (pinfunction "GND_GND") (pintype "power_in"))
      (node (ref "CN1") (pin "ID") (pinfunction "ID_ID") (pintype "bidirectional"))
      (node (ref "D1") (pin "A") (pinfunction "A_A") (pintype "passive"))
      (node (ref "G1") (pin "3") (pinfunction "S_3") (pintype "passive"))
      (node (ref "G10") (pin "3") (pinfunction "S_3") (pintype "passive"))
      (node (ref "G11") (pin "3") (pinfunction "S_3") (pintype "passive"))
      (node (ref "G12") (pin "3") (pinfunction "S_3") (pintype "passive"))
      (node (ref "G13") (pin "3") (pinfunction "S_3") (pintype "passive"))
      (node (ref "G14") (pin "3") (pinfunction "S_3") (pintype "passive"))
      (node (ref "G15") (pin "3") (pinfunction "S_3") (pintype "passive"))
      (node (ref "G16") (pin "3") (pinfunction "S_3") (pintype "passive"))
      (node (ref "G2") (pin "3") (pinfunction "S_3") (pintype "passive"))
      (node (ref "G3") (pin "3") (pinfunction "S_3") (pintype "passive"))
      (node (ref "G4") (pin "3") (pinfunction "S_3") (pintype "passive"))
      (node (ref "G5") (pin "3") (pinfunction "S_3") (pintype "passive"))
      (node (ref "G6") (pin "3") (pinfunction "S_3") (pintype "passive"))
      (node (ref "G7") (pin "3") (pinfunction "S_3") (pintype "passive"))
      (node (ref "G8") (pin "3") (pinfunction "S_3") (pintype "passive"))
      (node (ref "G9") (pin "3") (pinfunction "S_3") (pintype "passive"))
      (node (ref "J12") (pin "2") (pinfunction "2_2") (pintype "passive"))
      (node (ref "J8") (pin "2") (pinfunction "2_2") (pintype "passive"))
      (node (ref "JP1") (pin "1") (pinfunction "1_1") (pintype "passive"))
      (node (ref "JP2") (pin "2") (pinfunction "2_2") (pintype "passive"))
      (node (ref "LCD") (pin "4") (pinfunction "4_4") (pintype "passive"))
      (node (ref "LED1") (pin "C") (pinfunction "C_C") (pintype "passive"))
      (node (ref "LED10") (pin "C") (pinfunction "C_C") (pintype "passive"))
      (node (ref "LED11") (pin "C") (pinfunction "C_C") (pintype "passive"))
      (node (ref "LED12") (pin "C") (pinfunction "C_C") (pintype "passive"))
      (node (ref "LED13") (pin "C") (pinfunction "C_C") (pintype "passive"))
      (node (ref "LED14") (pin "C") (pinfunction "C_C") (pintype "passive"))
      (node (ref "LED15") (pin "C") (pinfunction "C_C") (pintype "passive"))
      (node (ref "LED16") (pin "C") (pinfunction "C_C") (pintype "passive"))
      (node (ref "LED17") (pin "C") (pinfunction "C_C") (pintype "passive"))
      (node (ref "LED18") (pin "C") (pinfunction "C_C") (pintype "passive"))
      (node (ref "LED2") (pin "C") (pinfunction "C_C") (pintype "passive"))
      (node (ref "LED20") (pin "C") (pinfunction "C_C") (pintype "passive"))
      (node (ref "LED3") (pin "C") (pinfunction "C_C") (pintype "passive"))
      (node (ref "LED4") (pin "C") (pinfunction "C_C") (pintype "passive"))
      (node (ref "LED5") (pin "C") (pinfunction "C_C") (pintype "passive"))
      (node (ref "LED6") (pin "C") (pinfunction "C_C") (pintype "passive"))
      (node (ref "LED7") (pin "C") (pinfunction "C_C") (pintype "passive"))
      (node (ref "LED8") (pin "C") (pinfunction "C_C") (pintype "passive"))
      (node (ref "LED9") (pin "C") (pinfunction "C_C") (pintype "passive"))
      (node (ref "Q3") (pin "2") (pinfunction "S_2") (pintype "passive"))
      (node (ref "R1") (pin "1") (pinfunction "1_1") (pintype "passive"))
      (node (ref "R10") (pin "1") (pinfunction "1_1") (pintype "passive"))
      (node (ref "R11") (pin "1") (pinfunction "1_1") (pintype "passive"))
      (node (ref "R12") (pin "1") (pinfunction "1_1") (pintype "passive"))
      (node (ref "R13") (pin "1") (pinfunction "1_1") (pintype "passive"))
      (node (ref "R14") (pin "1") (pinfunction "1_1") (pintype "passive"))
      (node (ref "R15") (pin "1") (pinfunction "1_1") (pintype "passive"))
      (node (ref "R16") (pin "1") (pinfunction "1_1") (pintype "passive"))
      (node (ref "R17") (pin "5") (pinfunction "2_5") (pintype "passive"))
      (node (ref "R17") (pin "6") (pinfunction "2_6") (pintype "passive"))
      (node (ref "R17") (pin "7") (pinfunction "2_7") (pintype "passive"))
      (node (ref "R17") (pin "8") (pinfunction "2_8") (pintype "passive"))
      (node (ref "R18") (pin "1") (pinfunction "1_1") (pintype "passive"))
      (node (ref "R18") (pin "2") (pinfunction "1_2") (pintype "passive"))
      (node (ref "R19") (pin "2") (pinfunction "2_2") (pintype "passive"))
      (node (ref "R2") (pin "1") (pinfunction "1_1") (pintype "passive"))
      (node (ref "R28") (pin "1") (pinfunction "1_1") (pintype "passive"))
      (node (ref "R3") (pin "1") (pinfunction "1_1") (pintype "passive"))
      (node (ref "R4") (pin "1") (pinfunction "1_1") (pintype "passive"))
      (node (ref "R47") (pin "1") (pinfunction "1_1") (pintype "passive"))
      (node (ref "R5") (pin "1") (pinfunction "1_1") (pintype "passive"))
      (node (ref "R53") (pin "1") (pinfunction "1_1") (pintype "passive"))
      (node (ref "R6") (pin "1") (pinfunction "1_1") (pintype "passive"))
      (node (ref "R7") (pin "1") (pinfunction "1_1") (pintype "passive"))
      (node (ref "R8") (pin "1") (pinfunction "1_1") (pintype "passive"))
      (node (ref "R9") (pin "1") (pinfunction "1_1") (pintype "passive"))
      (node (ref "S1") (pin "P$1") (pinfunction "P$1_P$1") (pintype "bidirectional"))
      (node (ref "S2") (pin "P$1") (pinfunction "P$1_P$1") (pintype "bidirectional"))
      (node (ref "U1") (pin "7") (pinfunction "GND_7") (pintype "passive"))
      (node (ref "U2") (pin "1") (pinfunction "GND_1") (pintype "power_in"))
      (node (ref "U2") (pin "15") (pinfunction "GND_15") (pintype "power_in"))
      (node (ref "U2") (pin "38") (pinfunction "GND_38") (pintype "power_in"))
      (node (ref "U2") (pin "39_1") (pinfunction "GND_39_1") (pintype "power_in"))
      (node (ref "U2") (pin "39_10") (pinfunction "GND_39_10") (pintype "power_in"))
      (node (ref "U2") (pin "39_11") (pinfunction "GND_39_11") (pintype "power_in"))
      (node (ref "U2") (pin "39_12") (pinfunction "GND_39_12") (pintype "power_in"))
      (node (ref "U2") (pin "39_13") (pinfunction "GND_39_13") (pintype "power_in"))
      (node (ref "U2") (pin "39_14") (pinfunction "GND_39_14") (pintype "power_in"))
      (node (ref "U2") (pin "39_15") (pinfunction "GND_39_15") (pintype "power_in"))
      (node (ref "U2") (pin "39_16") (pinfunction "GND_39_16") (pintype "power_in"))
      (node (ref "U2") (pin "39_17") (pinfunction "GND_39_17") (pintype "power_in"))
      (node (ref "U2") (pin "39_18") (pinfunction "GND_39_18") (pintype "power_in"))
      (node (ref "U2") (pin "39_19") (pinfunction "GND_39_19") (pintype "power_in"))
      (node (ref "U2") (pin "39_2") (pinfunction "GND_39_2") (pintype "power_in"))
      (node (ref "U2") (pin "39_20") (pinfunction "GND_39_20") (pintype "power_in"))
      (node (ref "U2") (pin "39_21") (pinfunction "GND_39_21") (pintype "power_in"))
      (node (ref "U2") (pin "39_3") (pinfunction "GND_39_3") (pintype "power_in"))
      (node (ref "U2") (pin "39_4") (pinfunction "GND_39_4") (pintype "power_in"))
      (node (ref "U2") (pin "39_5") (pinfunction "GND_39_5") (pintype "power_in"))
      (node (ref "U2") (pin "39_6") (pinfunction "GND_39_6") (pintype "power_in"))
      (node (ref "U2") (pin "39_7") (pinfunction "GND_39_7") (pintype "power_in"))
      (node (ref "U2") (pin "39_8") (pinfunction "GND_39_8") (pintype "power_in"))
      (node (ref "U2") (pin "39_9") (pinfunction "GND_39_9") (pintype "power_in"))
      (node (ref "U3") (pin "1") (pinfunction "GND_1") (pintype "bidirectional"))
      (node (ref "U4") (pin "1") (pinfunction "ADJ/GND_1") (pintype "power_in"))
      (node (ref "U5") (pin "4") (pinfunction "EN_4") (pintype "bidirectional"))
      (node (ref "U5") (pin "5") (pinfunction "GND_5") (pintype "bidirectional"))
      (node (ref "U5") (pin "6") (pinfunction "GND_6") (pintype "bidirectional"))
      (node (ref "U5") (pin "7") (pinfunction "GND_7") (pintype "bidirectional"))
      (node (ref "U5") (pin "8") (pinfunction "GND_8") (pintype "bidirectional"))
      (node (ref "U6") (pin "14") (pinfunction "VSS_14") (pintype "passive"))
      (node (ref "U7") (pin "7") (pinfunction "GND_7") (pintype "passive"))
      (node (ref "U8") (pin "7") (pinfunction "GND_7") (pintype "passive"))
      (node (ref "U9") (pin "2") (pinfunction "GND_2") (pintype "passive"))
      (node (ref "X1") (pin "3") (pinfunction "S_3") (pintype "passive"))
      (node (ref "X2") (pin "3") (pinfunction "S_3") (pintype "passive"))
    )
    (net (code "43") (name "Net-(C3-Pad+)") (class "Default")
      (node (ref "C3") (pin "+") (pinfunction "+_+") (pintype "passive"))
      (node (ref "D2") (pin "A") (pinfunction "A_A") (pintype "passive"))
      (node (ref "U4") (pin "2") (pinfunction "VOUT_2") (pintype "output"))
      (node (ref "U4") (pin "4") (pinfunction "VOUT_4") (pintype "output"))
    )
    (net (code "44") (name "Net-(G1-D)") (class "Default")
      (node (ref "CON1") (pin "P$2") (pinfunction "P$2_P$2") (pintype "bidirectional"))
      (node (ref "D3") (pin "1") (pinfunction "1_1") (pintype "bidirectional"))
      (node (ref "D3") (pin "3") (pinfunction "3_3") (pintype "bidirectional"))
      (node (ref "G1") (pin "2") (pinfunction "D_2") (pintype "passive"))
    )
    (net (code "45") (name "Net-(G2-D)") (class "Default")
      (node (ref "CON1") (pin "P$4") (pinfunction "P$4_P$4") (pintype "bidirectional"))
      (node (ref "D4") (pin "1") (pinfunction "1_1") (pintype "bidirectional"))
      (node (ref "D4") (pin "3") (pinfunction "3_3") (pintype "bidirectional"))
      (node (ref "G2") (pin "2") (pinfunction "D_2") (pintype "passive"))
    )
    (net (code "46") (name "Net-(G3-D)") (class "Default")
      (node (ref "CON1") (pin "P$6") (pinfunction "P$6_P$6") (pintype "bidirectional"))
      (node (ref "D5") (pin "1") (pinfunction "1_1") (pintype "bidirectional"))
      (node (ref "D5") (pin "3") (pinfunction "3_3") (pintype "bidirectional"))
      (node (ref "G3") (pin "2") (pinfunction "D_2") (pintype "passive"))
    )
    (net (code "47") (name "Net-(G4-D)") (class "Default")
      (node (ref "CON1") (pin "P$8") (pinfunction "P$8_P$8") (pintype "bidirectional"))
      (node (ref "D6") (pin "1") (pinfunction "1_1") (pintype "bidirectional"))
      (node (ref "D6") (pin "3") (pinfunction "3_3") (pintype "bidirectional"))
      (node (ref "G4") (pin "2") (pinfunction "D_2") (pintype "passive"))
    )
    (net (code "48") (name "Net-(G5-D)") (class "Default")
      (node (ref "CON1") (pin "P$10") (pinfunction "P$10_P$10") (pintype "bidirectional"))
      (node (ref "D7") (pin "1") (pinfunction "1_1") (pintype "bidirectional"))
      (node (ref "D7") (pin "3") (pinfunction "3_3") (pintype "bidirectional"))
      (node (ref "G5") (pin "2") (pinfunction "D_2") (pintype "passive"))
    )
    (net (code "49") (name "Net-(G6-D)") (class "Default")
      (node (ref "CON1") (pin "P$12") (pinfunction "P$12_P$12") (pintype "bidirectional"))
      (node (ref "D8") (pin "1") (pinfunction "1_1") (pintype "bidirectional"))
      (node (ref "D8") (pin "3") (pinfunction "3_3") (pintype "bidirectional"))
      (node (ref "G6") (pin "2") (pinfunction "D_2") (pintype "passive"))
    )
    (net (code "50") (name "Net-(G7-D)") (class "Default")
      (node (ref "CON1") (pin "P$14") (pinfunction "P$14_P$14") (pintype "bidirectional"))
      (node (ref "D9") (pin "1") (pinfunction "1_1") (pintype "bidirectional"))
      (node (ref "D9") (pin "3") (pinfunction "3_3") (pintype "bidirectional"))
      (node (ref "G7") (pin "2") (pinfunction "D_2") (pintype "passive"))
    )
    (net (code "51") (name "Net-(G8-D)") (class "Default")
      (node (ref "CON1") (pin "P$16") (pinfunction "P$16_P$16") (pintype "bidirectional"))
      (node (ref "D10") (pin "1") (pinfunction "1_1") (pintype "bidirectional"))
      (node (ref "D10") (pin "3") (pinfunction "3_3") (pintype "bidirectional"))
      (node (ref "G8") (pin "2") (pinfunction "D_2") (pintype "passive"))
    )
    (net (code "52") (name "Net-(G9-D)") (class "Default")
      (node (ref "CON2") (pin "P$2") (pinfunction "P$2_P$2") (pintype "bidirectional"))
      (node (ref "D11") (pin "1") (pinfunction "1_1") (pintype "bidirectional"))
      (node (ref "D11") (pin "3") (pinfunction "3_3") (pintype "bidirectional"))
      (node (ref "G9") (pin "2") (pinfunction "D_2") (pintype "passive"))
    )
    (net (code "53") (name "Net-(G10-D)") (class "Default")
      (node (ref "CON2") (pin "P$4") (pinfunction "P$4_P$4") (pintype "bidirectional"))
      (node (ref "D12") (pin "1") (pinfunction "1_1") (pintype "bidirectional"))
      (node (ref "D12") (pin "3") (pinfunction "3_3") (pintype "bidirectional"))
      (node (ref "G10") (pin "2") (pinfunction "D_2") (pintype "passive"))
    )
    (net (code "54") (name "Net-(G11-D)") (class "Default")
      (node (ref "CON2") (pin "P$6") (pinfunction "P$6_P$6") (pintype "bidirectional"))
      (node (ref "D13") (pin "1") (pinfunction "1_1") (pintype "bidirectional"))
      (node (ref "D13") (pin "3") (pinfunction "3_3") (pintype "bidirectional"))
      (node (ref "G11") (pin "2") (pinfunction "D_2") (pintype "passive"))
    )
    (net (code "55") (name "Net-(G12-D)") (class "Default")
      (node (ref "CON2") (pin "P$8") (pinfunction "P$8_P$8") (pintype "bidirectional"))
      (node (ref "D14") (pin "1") (pinfunction "1_1") (pintype "bidirectional"))
      (node (ref "D14") (pin "3") (pinfunction "3_3") (pintype "bidirectional"))
      (node (ref "G12") (pin "2") (pinfunction "D_2") (pintype "passive"))
    )
    (net (code "56") (name "Net-(G13-D)") (class "Default")
      (node (ref "CON2") (pin "P$10") (pinfunction "P$10_P$10") (pintype "bidirectional"))
      (node (ref "D15") (pin "1") (pinfunction "1_1") (pintype "bidirectional"))
      (node (ref "D15") (pin "3") (pinfunction "3_3") (pintype "bidirectional"))
      (node (ref "G13") (pin "2") (pinfunction "D_2") (pintype "passive"))
    )
    (net (code "57") (name "Net-(G14-D)") (class "Default")
      (node (ref "CON2") (pin "P$12") (pinfunction "P$12_P$12") (pintype "bidirectional"))
      (node (ref "D16") (pin "1") (pinfunction "1_1") (pintype "bidirectional"))
      (node (ref "D16") (pin "3") (pinfunction "3_3") (pintype "bidirectional"))
      (node (ref "G14") (pin "2") (pinfunction "D_2") (pintype "passive"))
    )
    (net (code "58") (name "Net-(G15-D)") (class "Default")
      (node (ref "CON2") (pin "P$14") (pinfunction "P$14_P$14") (pintype "bidirectional"))
      (node (ref "D17") (pin "1") (pinfunction "1_1") (pintype "bidirectional"))
      (node (ref "D17") (pin "3") (pinfunction "3_3") (pintype "bidirectional"))
      (node (ref "G15") (pin "2") (pinfunction "D_2") (pintype "passive"))
    )
    (net (code "59") (name "Net-(G16-D)") (class "Default")
      (node (ref "CON2") (pin "P$16") (pinfunction "P$16_P$16") (pintype "bidirectional"))
      (node (ref "D18") (pin "1") (pinfunction "1_1") (pintype "bidirectional"))
      (node (ref "D18") (pin "3") (pinfunction "3_3") (pintype "bidirectional"))
      (node (ref "G16") (pin "2") (pinfunction "D_2") (pintype "passive"))
    )
    (net (code "60") (name "Net-(LED1-PadA)") (class "Default")
      (node (ref "LED1") (pin "A") (pinfunction "A_A") (pintype "passive"))
      (node (ref "R20") (pin "1") (pinfunction "1_1") (pintype "passive"))
    )
    (net (code "61") (name "Net-(LED5-PadA)") (class "Default")
      (node (ref "LED5") (pin "A") (pinfunction "A_A") (pintype "passive"))
      (node (ref "R21") (pin "1") (pinfunction "1_1") (pintype "passive"))
    )
    (net (code "62") (name "Net-(LED9-PadA)") (class "Default")
      (node (ref "LED9") (pin "A") (pinfunction "A_A") (pintype "passive"))
      (node (ref "R22") (pin "1") (pinfunction "1_1") (pintype "passive"))
    )
    (net (code "63") (name "Net-(LED13-PadA)") (class "Default")
      (node (ref "LED13") (pin "A") (pinfunction "A_A") (pintype "passive"))
      (node (ref "R23") (pin "1") (pinfunction "1_1") (pintype "passive"))
    )
    (net (code "64") (name "Net-(LED17-PadA)") (class "Default")
      (node (ref "LED17") (pin "A") (pinfunction "A_A") (pintype "passive"))
      (node (ref "R51") (pin "1") (pinfunction "1_1") (pintype "passive"))
    )
    (net (code "65") (name "Net-(LED18-PadA)") (class "Default")
      (node (ref "LED18") (pin "A") (pinfunction "A_A") (pintype "passive"))
      (node (ref "R50") (pin "1") (pinfunction "1_1") (pintype "passive"))
    )
    (net (code "66") (name "Net-(LED20-PadA)") (class "Default")
      (node (ref "LED20") (pin "A") (pinfunction "A_A") (pintype "passive"))
      (node (ref "R57") (pin "1") (pinfunction "1_1") (pintype "passive"))
    )
    (net (code "67") (name "Net-(Q1-B)") (class "Default")
      (node (ref "Q1") (pin "1") (pinfunction "B_1") (pintype "passive"))
      (node (ref "R25") (pin "2") (pinfunction "2_2") (pintype "passive"))
    )
    (net (code "68") (name "Net-(Q1-E)") (class "Default")
      (node (ref "Q1") (pin "2") (pinfunction "E_2") (pintype "passive"))
      (node (ref "R26") (pin "1") (pinfunction "1_1") (pintype "passive"))
      (node (ref "U3") (pin "13") (pinfunction "~{DTR}_13") (pintype "bidirectional"))
    )
    (net (code "69") (name "Net-(Q2-B)") (class "Default")
      (node (ref "Q2") (pin "1") (pinfunction "B_1") (pintype "passive"))
      (node (ref "R26") (pin "2") (pinfunction "2_2") (pintype "passive"))
    )
    (net (code "70") (name "Net-(Q2-E)") (class "Default")
      (node (ref "Q2") (pin "2") (pinfunction "E_2") (pintype "passive"))
      (node (ref "R25") (pin "1") (pinfunction "1_1") (pintype "passive"))
      (node (ref "U3") (pin "14") (pinfunction "~{RTS}_14") (pintype "bidirectional"))
    )
    (net (code "71") (name "Net-(Q3-D)") (class "Default")
      (node (ref "JP2") (pin "1") (pinfunction "1_1") (pintype "passive"))
      (node (ref "Q3") (pin "3") (pinfunction "D_3") (pintype "passive"))
      (node (ref "Q4") (pin "3") (pinfunction "D_3") (pintype "passive"))
    )
    (net (code "72") (name "Net-(R18C-2)") (class "Default")
      (node (ref "J9") (pin "2") (pinfunction "2_2") (pintype "passive"))
      (node (ref "R18") (pin "6") (pinfunction "2_6") (pintype "passive"))
    )
    (net (code "73") (name "Net-(R18D-2)") (class "Default")
      (node (ref "J10") (pin "2") (pinfunction "2_2") (pintype "passive"))
      (node (ref "R18") (pin "5") (pinfunction "2_5") (pintype "passive"))
    )
    (net (code "74") (name "Net-(R20B-1)") (class "Default")
      (node (ref "LED2") (pin "A") (pinfunction "A_A") (pintype "passive"))
      (node (ref "R20") (pin "2") (pinfunction "1_2") (pintype "passive"))
    )
    (net (code "75") (name "Net-(R20C-1)") (class "Default")
      (node (ref "LED3") (pin "A") (pinfunction "A_A") (pintype "passive"))
      (node (ref "R20") (pin "3") (pinfunction "1_3") (pintype "passive"))
    )
    (net (code "76") (name "Net-(R20D-1)") (class "Default")
      (node (ref "LED4") (pin "A") (pinfunction "A_A") (pintype "passive"))
      (node (ref "R20") (pin "4") (pinfunction "1_4") (pintype "passive"))
    )
    (net (code "77") (name "Net-(R21B-1)") (class "Default")
      (node (ref "LED6") (pin "A") (pinfunction "A_A") (pintype "passive"))
      (node (ref "R21") (pin "2") (pinfunction "1_2") (pintype "passive"))
    )
    (net (code "78") (name "Net-(R21C-1)") (class "Default")
      (node (ref "LED7") (pin "A") (pinfunction "A_A") (pintype "passive"))
      (node (ref "R21") (pin "3") (pinfunction "1_3") (pintype "passive"))
    )
    (net (code "79") (name "Net-(R21D-1)") (class "Default")
      (node (ref "LED8") (pin "A") (pinfunction "A_A") (pintype "passive"))
      (node (ref "R21") (pin "4") (pinfunction "1_4") (pintype "passive"))
    )
    (net (code "80") (name "Net-(R22B-1)") (class "Default")
      (node (ref "LED10") (pin "A") (pinfunction "A_A") (pintype "passive"))
      (node (ref "R22") (pin "2") (pinfunction "1_2") (pintype "passive"))
    )
    (net (code "81") (name "Net-(R22C-1)") (class "Default")
      (node (ref "LED11") (pin "A") (pinfunction "A_A") (pintype "passive"))
      (node (ref "R22") (pin "3") (pinfunction "1_3") (pintype "passive"))
    )
    (net (code "82") (name "Net-(R22D-1)") (class "Default")
      (node (ref "LED12") (pin "A") (pinfunction "A_A") (pintype "passive"))
      (node (ref "R22") (pin "4") (pinfunction "1_4") (pintype "passive"))
    )
    (net (code "83") (name "Net-(R23B-1)") (class "Default")
      (node (ref "LED14") (pin "A") (pinfunction "A_A") (pintype "passive"))
      (node (ref "R23") (pin "2") (pinfunction "1_2") (pintype "passive"))
    )
    (net (code "84") (name "Net-(R23C-1)") (class "Default")
      (node (ref "LED15") (pin "A") (pinfunction "A_A") (pintype "passive"))
      (node (ref "R23") (pin "3") (pinfunction "1_3") (pintype "passive"))
    )
    (net (code "85") (name "Net-(R23D-1)") (class "Default")
      (node (ref "LED16") (pin "A") (pinfunction "A_A") (pintype "passive"))
      (node (ref "R23") (pin "4") (pinfunction "1_4") (pintype "passive"))
    )
    (net (code "86") (name "Net-(U1-1A)") (class "Default")
      (node (ref "U1") (pin "1") (pinfunction "1A_1") (pintype "input"))
      (node (ref "U6") (pin "6") (pinfunction "LED0_6") (pintype "output"))
    )
    (net (code "87") (name "Net-(U1-2A)") (class "Default")
      (node (ref "U1") (pin "3") (pinfunction "2A_3") (pintype "input"))
      (node (ref "U6") (pin "7") (pinfunction "LED1_7") (pintype "output"))
    )
    (net (code "88") (name "Net-(U1-3A)") (class "Default")
      (node (ref "U1") (pin "5") (pinfunction "3A_5") (pintype "input"))
      (node (ref "U6") (pin "8") (pinfunction "LED2_8") (pintype "output"))
    )
    (net (code "89") (name "Net-(U1-4A)") (class "Default")
      (node (ref "U1") (pin "9") (pinfunction "4A_9") (pintype "input"))
      (node (ref "U6") (pin "9") (pinfunction "LED3_9") (pintype "output"))
    )
    (net (code "90") (name "Net-(U1-5A)") (class "Default")
      (node (ref "U1") (pin "11") (pinfunction "5A_11") (pintype "input"))
      (node (ref "U6") (pin "10") (pinfunction "LED4_10") (pintype "output"))
    )
    (net (code "91") (name "Net-(U1-6A)") (class "Default")
      (node (ref "U1") (pin "13") (pinfunction "6A_13") (pintype "input"))
      (node (ref "U6") (pin "11") (pinfunction "LED5_11") (pintype "output"))
    )
    (net (code "92") (name "Net-(U3-RXI)") (class "Default")
      (node (ref "R49") (pin "1") (pinfunction "1_1") (pintype "passive"))
      (node (ref "U3") (pin "3") (pinfunction "RXI_3") (pintype "bidirectional"))
    )
    (net (code "93") (name "Net-(U3-TXO)") (class "Default")
      (node (ref "R48") (pin "1") (pinfunction "1_1") (pintype "passive"))
      (node (ref "U3") (pin "2") (pinfunction "TXO_2") (pintype "bidirectional"))
    )
    (net (code "94") (name "Net-(U3-UD+)") (class "Default")
      (node (ref "CN1") (pin "D+") (pinfunction "D+_D+") (pintype "bidirectional"))
      (node (ref "U3") (pin "5") (pinfunction "UD+_5") (pintype "bidirectional"))
    )
    (net (code "95") (name "Net-(U3-UD-)") (class "Default")
      (node (ref "CN1") (pin "D-") (pinfunction "D-_D-") (pintype "bidirectional"))
      (node (ref "U3") (pin "6") (pinfunction "UD-_6") (pintype "bidirectional"))
    )
    (net (code "96") (name "Net-(U5-FB)") (class "Default")
      (node (ref "C29") (pin "2") (pinfunction "2_2") (pintype "passive"))
      (node (ref "R27") (pin "1") (pinfunction "1_1") (pintype "passive"))
      (node (ref "R28") (pin "2") (pinfunction "2_2") (pintype "passive"))
      (node (ref "R29") (pin "1") (pinfunction "1_1") (pintype "passive"))
      (node (ref "U5") (pin "3") (pinfunction "FB_3") (pintype "bidirectional"))
    )
    (net (code "97") (name "Net-(U5-SW)") (class "Default")
      (node (ref "D1") (pin "C") (pinfunction "C_C") (pintype "passive"))
      (node (ref "L1") (pin "P$1") (pinfunction "P$1_P$1") (pintype "bidirectional"))
      (node (ref "U5") (pin "2") (pinfunction "SW_2") (pintype "bidirectional"))
    )
    (net (code "98") (name "Net-(U6-LED6)") (class "Default")
      (node (ref "U6") (pin "12") (pinfunction "LED6_12") (pintype "output"))
      (node (ref "U7") (pin "1") (pinfunction "1A_1") (pintype "input"))
    )
    (net (code "99") (name "Net-(U6-LED7)") (class "Default")
      (node (ref "U6") (pin "13") (pinfunction "LED7_13") (pintype "output"))
      (node (ref "U7") (pin "3") (pinfunction "2A_3") (pintype "input"))
    )
    (net (code "100") (name "Net-(U6-LED8)") (class "Default")
      (node (ref "U6") (pin "15") (pinfunction "LED8_15") (pintype "output"))
      (node (ref "U7") (pin "5") (pinfunction "3A_5") (pintype "input"))
    )
    (net (code "101") (name "Net-(U6-LED9)") (class "Default")
      (node (ref "U6") (pin "16") (pinfunction "LED9_16") (pintype "output"))
      (node (ref "U7") (pin "9") (pinfunction "4A_9") (pintype "input"))
    )
    (net (code "102") (name "Net-(U6-LED10)") (class "Default")
      (node (ref "U6") (pin "17") (pinfunction "LED10_17") (pintype "output"))
      (node (ref "U7") (pin "11") (pinfunction "5A_11") (pintype "input"))
    )
    (net (code "103") (name "Net-(U6-LED11)") (class "Default")
      (node (ref "U6") (pin "18") (pinfunction "LED11_18") (pintype "output"))
      (node (ref "U7") (pin "13") (pinfunction "6A_13") (pintype "input"))
    )
    (net (code "104") (name "Net-(U6-LED12)") (class "Default")
      (node (ref "U6") (pin "19") (pinfunction "LED12_19") (pintype "output"))
      (node (ref "U8") (pin "1") (pinfunction "1A_1") (pintype "input"))
    )
    (net (code "105") (name "Net-(U6-LED13)") (class "Default")
      (node (ref "U6") (pin "20") (pinfunction "LED13_20") (pintype "output"))
      (node (ref "U8") (pin "3") (pinfunction "2A_3") (pintype "input"))
    )
    (net (code "106") (name "Net-(U6-LED14)") (class "Default")
      (node (ref "U6") (pin "21") (pinfunction "LED14_21") (pintype "output"))
      (node (ref "U8") (pin "5") (pinfunction "3A_5") (pintype "input"))
    )
    (net (code "107") (name "Net-(U6-LED15)") (class "Default")
      (node (ref "U6") (pin "22") (pinfunction "LED15_22") (pintype "output"))
      (node (ref "U8") (pin "9") (pinfunction "4A_9") (pintype "input"))
    )
    (net (code "108") (name "V+") (class "Default")
      (node (ref "C13") (pin "+") (pinfunction "+_+") (pintype "passive"))
      (node (ref "C14") (pin "+") (pinfunction "+_+") (pintype "passive"))
      (node (ref "C15") (pin "+") (pinfunction "+_+") (pintype "passive"))
      (node (ref "CON1") (pin "P$1") (pinfunction "P$1_P$1") (pintype "bidirectional"))
      (node (ref "CON1") (pin "P$11") (pinfunction "P$11_P$11") (pintype "bidirectional"))
      (node (ref "CON1") (pin "P$13") (pinfunction "P$13_P$13") (pintype "bidirectional"))
      (node (ref "CON1") (pin "P$15") (pinfunction "P$15_P$15") (pintype "bidirectional"))
      (node (ref "CON1") (pin "P$3") (pinfunction "P$3_P$3") (pintype "bidirectional"))
      (node (ref "CON1") (pin "P$5") (pinfunction "P$5_P$5") (pintype "bidirectional"))
      (node (ref "CON1") (pin "P$7") (pinfunction "P$7_P$7") (pintype "bidirectional"))
      (node (ref "CON1") (pin "P$9") (pinfunction "P$9_P$9") (pintype "bidirectional"))
      (node (ref "CON2") (pin "P$1") (pinfunction "P$1_P$1") (pintype "bidirectional"))
      (node (ref "CON2") (pin "P$11") (pinfunction "P$11_P$11") (pintype "bidirectional"))
      (node (ref "CON2") (pin "P$13") (pinfunction "P$13_P$13") (pintype "bidirectional"))
      (node (ref "CON2") (pin "P$15") (pinfunction "P$15_P$15") (pintype "bidirectional"))
      (node (ref "CON2") (pin "P$3") (pinfunction "P$3_P$3") (pintype "bidirectional"))
      (node (ref "CON2") (pin "P$5") (pinfunction "P$5_P$5") (pintype "bidirectional"))
      (node (ref "CON2") (pin "P$7") (pinfunction "P$7_P$7") (pintype "bidirectional"))
      (node (ref "CON2") (pin "P$9") (pinfunction "P$9_P$9") (pintype "bidirectional"))
      (node (ref "D10") (pin "2") (pinfunction "2_2") (pintype "bidirectional"))
      (node (ref "D11") (pin "2") (pinfunction "2_2") (pintype "bidirectional"))
      (node (ref "D12") (pin "2") (pinfunction "2_2") (pintype "bidirectional"))
      (node (ref "D13") (pin "2") (pinfunction "2_2") (pintype "bidirectional"))
      (node (ref "D14") (pin "2") (pinfunction "2_2") (pintype "bidirectional"))
      (node (ref "D15") (pin "2") (pinfunction "2_2") (pintype "bidirectional"))
      (node (ref "D16") (pin "2") (pinfunction "2_2") (pintype "bidirectional"))
      (node (ref "D17") (pin "2") (pinfunction "2_2") (pintype "bidirectional"))
      (node (ref "D18") (pin "2") (pinfunction "2_2") (pintype "bidirectional"))
      (node (ref "D3") (pin "2") (pinfunction "2_2") (pintype "bidirectional"))
      (node (ref "D4") (pin "2") (pinfunction "2_2") (pintype "bidirectional"))
      (node (ref "D5") (pin "2") (pinfunction "2_2") (pintype "bidirectional"))
      (node (ref "D6") (pin "2") (pinfunction "2_2") (pintype "bidirectional"))
      (node (ref "D7") (pin "2") (pinfunction "2_2") (pintype "bidirectional"))
      (node (ref "D8") (pin "2") (pinfunction "2_2") (pintype "bidirectional"))
      (node (ref "D9") (pin "2") (pinfunction "2_2") (pintype "bidirectional"))
      (node (ref "F1") (pin "2_1") (pinfunction "2_2_1") (pintype "passive"))
      (node (ref "F1") (pin "2_2") (pinfunction "2_2_2") (pintype "passive"))
    )
    (net (code "109") (name "VCC") (class "Default")
      (node (ref "F1") (pin "1_1") (pinfunction "1_1_1") (pintype "passive"))
      (node (ref "F1") (pin "1_2") (pinfunction "1_1_2") (pintype "passive"))
      (node (ref "J8") (pin "1") (pinfunction "1_1") (pintype "passive"))
    )
    (net (code "110") (name "VDD") (class "Default")
      (node (ref "C6") (pin "+") (pinfunction "+_+") (pintype "passive"))
      (node (ref "J12") (pin "1") (pinfunction "1_1") (pintype "passive"))
      (node (ref "U5") (pin "1") (pinfunction "VIN_1") (pintype "bidirectional"))
    )
    (net (code "111") (name "unconnected-(U2-IO5-Pad29)") (class "Default")
      (node (ref "U2") (pin "29") (pinfunction "IO5_29") (pintype "bidirectional"))
    )
    (net (code "112") (name "unconnected-(U2-IO12-Pad14)") (class "Default")
      (node (ref "U2") (pin "14") (pinfunction "IO12_14") (pintype "bidirectional"))
    )
    (net (code "113") (name "unconnected-(U2-IO13-Pad16)") (class "Default")
      (node (ref "U2") (pin "16") (pinfunction "IO13_16") (pintype "bidirectional"))
    )
    (net (code "114") (name "unconnected-(U2-IO14-Pad13)") (class "Default")
      (node (ref "U2") (pin "13") (pinfunction "IO14_13") (pintype "bidirectional"))
    )
    (net (code "115") (name "unconnected-(U2-IO15-Pad23)") (class "Default")
      (node (ref "U2") (pin "23") (pinfunction "IO15_23") (pintype "bidirectional"))
    )
    (net (code "116") (name "unconnected-(U2-IO26-Pad11)") (class "Default")
      (node (ref "U2") (pin "11") (pinfunction "IO26_11") (pintype "bidirectional"))
    )
    (net (code "117") (name "unconnected-(U2-IO27-Pad12)") (class "Default")
      (node (ref "U2") (pin "12") (pinfunction "IO27_12") (pintype "bidirectional"))
    )
    (net (code "118") (name "unconnected-(U2-IO34-Pad6)") (class "Default")
      (node (ref "U2") (pin "6") (pinfunction "IO34_6") (pintype "input"))
    )
    (net (code "119") (name "unconnected-(U2-IO35-Pad7)") (class "Default")
      (node (ref "U2") (pin "7") (pinfunction "IO35_7") (pintype "input"))
    )
    (net (code "120") (name "unconnected-(U2-NC-Pad32)") (class "Default")
      (node (ref "U2") (pin "32") (pinfunction "NC_32") (pintype "no_connect"))
    )
    (net (code "121") (name "unconnected-(U2-SCK{slash}CLK-Pad20)") (class "Default")
      (node (ref "U2") (pin "20") (pinfunction "SCK/CLK_20") (pintype "bidirectional"))
    )
    (net (code "122") (name "unconnected-(U2-SCS{slash}CMD-Pad19)") (class "Default")
      (node (ref "U2") (pin "19") (pinfunction "SCS/CMD_19") (pintype "bidirectional"))
    )
    (net (code "123") (name "unconnected-(U2-SDI{slash}SD1-Pad22)") (class "Default")
      (node (ref "U2") (pin "22") (pinfunction "SDI/SD1_22") (pintype "bidirectional"))
    )
    (net (code "124") (name "unconnected-(U2-SDO{slash}SD0-Pad21)") (class "Default")
      (node (ref "U2") (pin "21") (pinfunction "SDO/SD0_21") (pintype "bidirectional"))
    )
    (net (code "125") (name "unconnected-(U2-SENSOR_VN-Pad5)") (class "Default")
      (node (ref "U2") (pin "5") (pinfunction "SENSOR_VN_5") (pintype "input"))
    )
    (net (code "126") (name "unconnected-(U2-SENSOR_VP-Pad4)") (class "Default")
      (node (ref "U2") (pin "4") (pinfunction "SENSOR_VP_4") (pintype "input"))
    )
    (net (code "127") (name "unconnected-(U2-SHD{slash}SD2-Pad17)") (class "Default")
      (node (ref "U2") (pin "17") (pinfunction "SHD/SD2_17") (pintype "bidirectional"))
    )
    (net (code "128") (name "unconnected-(U2-SWP{slash}SD3-Pad18)") (class "Default")
      (node (ref "U2") (pin "18") (pinfunction "SWP/SD3_18") (pintype "bidirectional"))
    )
    (net (code "129") (name "unconnected-(U3-R232-Pad15)") (class "Default")
      (node (ref "U3") (pin "15") (pinfunction "R232_15") (pintype "bidirectional"))
    )
    (net (code "130") (name "unconnected-(U3-~{CTS}-Pad9)") (class "Default")
      (node (ref "U3") (pin "9") (pinfunction "~{CTS}_9") (pintype "bidirectional"))
    )
    (net (code "131") (name "unconnected-(U3-~{DCD}-Pad12)") (class "Default")
      (node (ref "U3") (pin "12") (pinfunction "~{DCD}_12") (pintype "bidirectional"))
    )
    (net (code "132") (name "unconnected-(U3-~{DSR}-Pad10)") (class "Default")
      (node (ref "U3") (pin "10") (pinfunction "~{DSR}_10") (pintype "bidirectional"))
    )
    (net (code "133") (name "unconnected-(U3-~{RI}-Pad11)") (class "Default")
      (node (ref "U3") (pin "11") (pinfunction "~{RI}_11") (pintype "bidirectional"))
    )
    (net (code "134") (name "unconnected-(U8-5A-Pad11)") (class "Default")
      (node (ref "U8") (pin "11") (pinfunction "5A_11") (pintype "input"))
    )
    (net (code "135") (name "unconnected-(U8-5Y-Pad10)") (class "Default")
      (node (ref "U8") (pin "10") (pinfunction "5Y_10") (pintype "output"))
    )
    (net (code "136") (name "unconnected-(U8-6A-Pad13)") (class "Default")
      (node (ref "U8") (pin "13") (pinfunction "6A_13") (pintype "input"))
    )
    (net (code "137") (name "unconnected-(U8-6Y-Pad12)") (class "Default")
      (node (ref "U8") (pin "12") (pinfunction "6Y_12") (pintype "output"))
    )
    (net (code "138") (name "unconnected-(U9-NC-Pad3)") (class "Default")
      (node (ref "U9") (pin "3") (pinfunction "NC_3") (pintype "no_connect"))
    )
  )
)
